# ATSAM3X8E_Main_Controller_-_TR_R1_1.net
KiCad netlist of a schematic drawn in Altium Designer
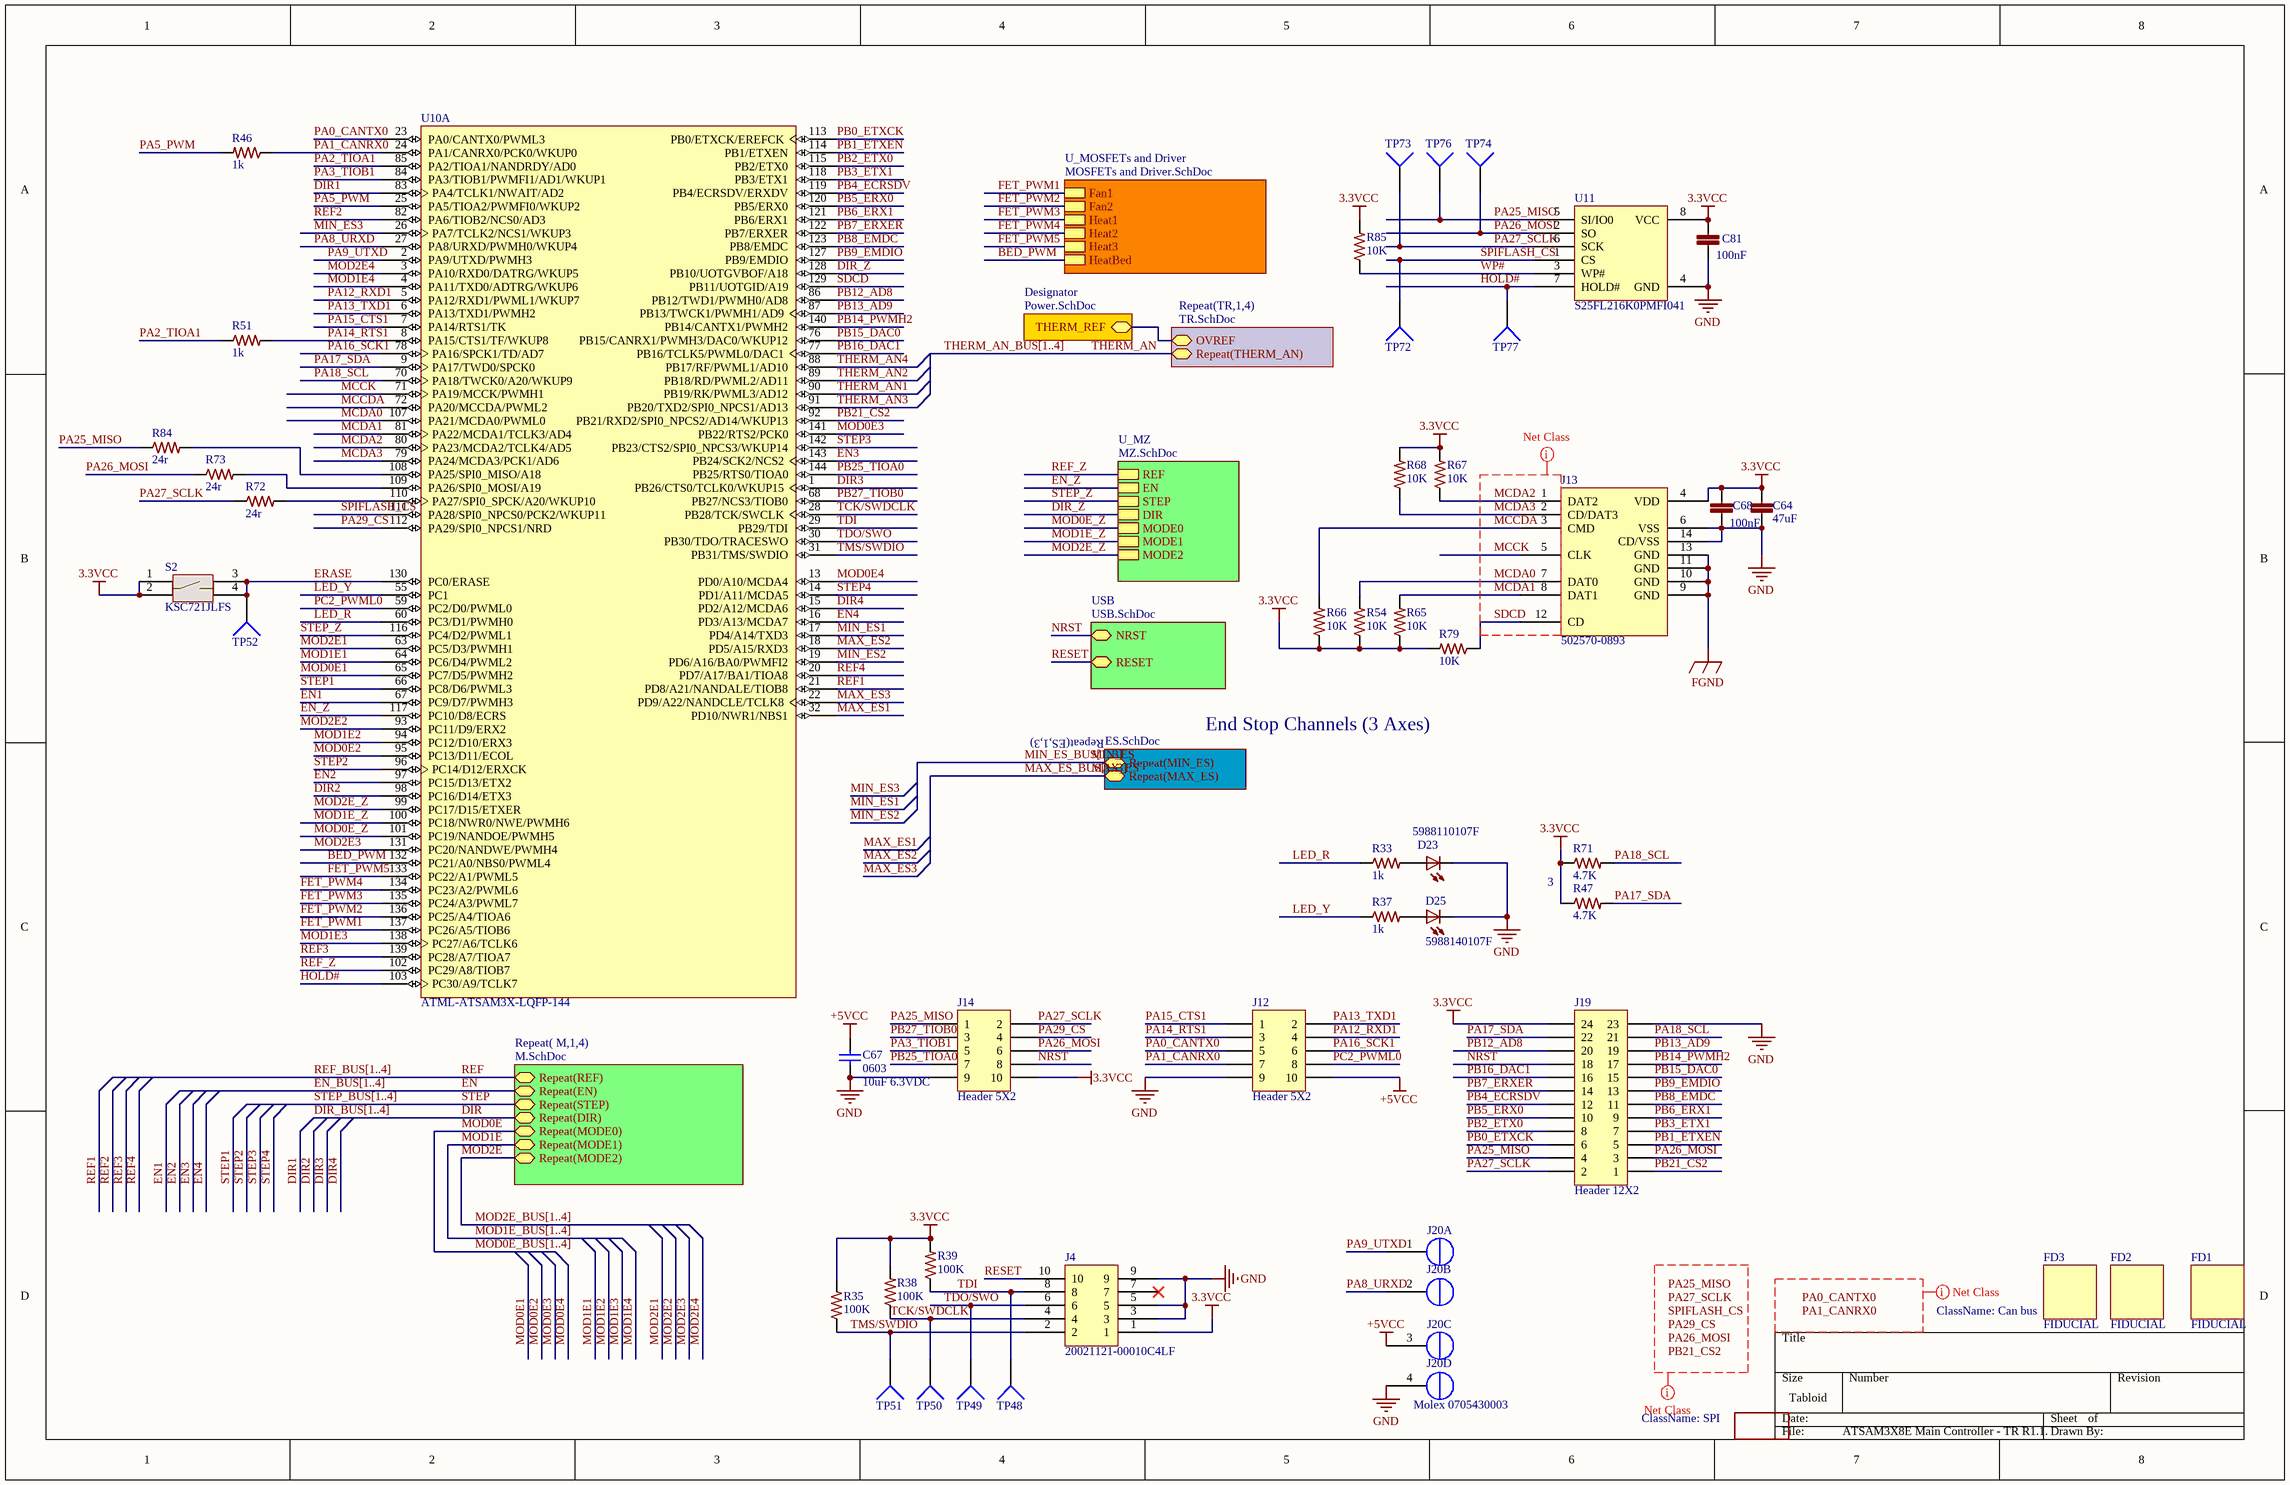
[diagram p0: ATSAM3X8E Main Controller - TR R1.1.SchDoc]

(export (version "E")
  (design (tool "Eeschema 10.0.6"))
  (components
    (comp (ref "C64")
      (value "47uF")
      (footprint "C0805")
      (description "CAP CER 47UF 6.3V 20% X5R 0805")
      (fields
        (field (name "MANUFACTURER") "Samsung")
        (field (name "MANUFACTURERPARTNUMBER") "CL21A476MQCLRNC")
        (field (name "PUBLISHER") "UltiMachine")
      )
      (libsource (lib "Tigershark3D") (part "CL21A476MQCLRNC"))
    )
    (comp (ref "C67")
      (value "0603")
      (footprint "C0603")
      (description "CAP CER 10UF 6.3V 10% JB 0603")
      (fields
        (field (name "MFR PART #") "C1608JB0J106K080AB")
        (field (name "MFR") "TDK")
        (field (name "ALTIUM_VALUE") "10uF 6.3VDC")
      )
      (libsource (lib "Tigershark3D") (part "C1608JB0J106K080AB"))
    )
    (comp (ref "C68")
      (value "100nF")
      (footprint "C0402")
      (description "CAP CER 0402 100nF 16V 10% X7R")
      (fields
        (field (name "MANUFACTURERPARTNUMBER") "GRM155R71C104KA88D")
        (field (name "PUBLISHER") "UltiMachine")
      )
      (libsource (lib "3Delight") (part "GRM155R71C104KA88D"))
    )
    (comp (ref "C81")
      (value "100nF")
      (footprint "C0402")
      (description "CAP CER 0402 100nF 16V 10% X7R")
      (fields
        (field (name "MANUFACTURERPARTNUMBER") "GRM155R71C104KA88D")
        (field (name "PUBLISHER") "UltiMachine")
      )
      (libsource (lib "3Delight") (part "GRM155R71C104KA88D"))
    )
    (comp (ref "D23")
      (value "5988110107F")
      (footprint "LED2012120")
      (description "LED 0805 Red")
      (fields (field (name "PUBLISHER") "UltiMachine"))
      (libsource (lib "3Delight") (part "5988110107F"))
    )
    (comp (ref "D25")
      (value "5988140107F")
      (footprint "LED2012120")
      (description "LED 0805 Yellow")
      (fields (field (name "PUBLISHER") "UltiMachine"))
      (libsource (lib "3Delight") (part "5988140107F"))
    )
    (comp (ref "FD1")
      (value "FIDUCIAL")
      (footprint "FIDUCIAL-1X2")
      (libsource (lib "3Delight") (part "FIDUCIAL"))
    )
    (comp (ref "FD2")
      (value "FIDUCIAL")
      (footprint "FIDUCIAL-1X2")
      (libsource (lib "3Delight") (part "FIDUCIAL"))
    )
    (comp (ref "FD3")
      (value "FIDUCIAL")
      (footprint "FIDUCIAL-1X2")
      (libsource (lib "3Delight") (part "FIDUCIAL"))
    )
    (comp (ref "J4")
      (value "20021121-00010C4LF")
      (footprint "FTSH-105-XX-X-DV")
      (libsource (lib "Adams Altium Library") (part "ARM Cortex JTAG-DEBUG Header"))
    )
    (comp (ref "J12")
      (value "Header 5X2")
      (footprint "HDR2X5")
      (description "Header, 5-Pin, Dual row")
      (fields (field (name "PUBLISHER") "Altium Limited"))
      (libsource (lib "Miscellaneous Connectors") (part "Header 5X2"))
    )
    (comp (ref "J13")
      (value "502570-0893")
      (footprint "502570-0893 - Molex SD")
      (description "microSD 502570-0893 Molex Part")
      (libsource (lib "Tigershark3D") (part "502570-0893"))
    )
    (comp (ref "J14")
      (value "Header 5X2")
      (footprint "HDR2X5")
      (description "Header, 5-Pin, Dual row")
      (fields (field (name "PUBLISHER") "Altium Limited"))
      (libsource (lib "Miscellaneous Connectors") (part "Header 5X2"))
    )
    (comp (ref "J19")
      (value "Header 12X2")
      (footprint "HDR2X12")
      (description "Header, 12-Pin, Dual row")
      (fields (field (name "PUBLISHER") "Altium Limited"))
      (libsource (lib "Miscellaneous Connectors") (part "Header 12X2"))
    )
    (comp (ref "J20")
      (value "Molex 0705430003")
      (footprint "Molex 0705430003")
      (description "Molex 4 Pin Clip Connector")
      (libsource (lib "ZMBo Schematic Library") (part "Molex 0705430003 Alt"))
    )
    (comp (ref "LOGO1")
      (value "OSHW_LOGO_8MILX0150-NT")
      (footprint "OSHW_8X150_NOTEXT")
      (fields (field (name "PUBLISHER") "UltiMachine"))
      (libsource (lib "3Delight") (part "OSHW_LOGO_8MILX0150-NT"))
    )
    (comp (ref "R33")
      (value "1k")
      (footprint "R0402")
      (description "RES 0402 1k 63mW 1%")
      (fields (field (name "PUBLISHER") "UltiMachine"))
      (libsource (lib "3Delight") (part "RK73H1ETTP1001F"))
    )
    (comp (ref "R35")
      (value "100K")
      (footprint "3Delight:R0402")
      (description "RES SMD 100K OHM 1% 1/16W 0402")
      (fields
        (field (name "MANUFACTURER") "Samsung")
        (field (name "MANUFACTURERPARTNUMBER") "RC1005F104CS")
        (field (name "PUBLISHER") "UltiMachine")
      )
      (libsource (lib "Tigershark3D") (part "RC1005F104CS"))
    )
    (comp (ref "R37")
      (value "1k")
      (footprint "R0402")
      (description "RES 0402 1k 63mW 1%")
      (fields (field (name "PUBLISHER") "UltiMachine"))
      (libsource (lib "3Delight") (part "RK73H1ETTP1001F"))
    )
    (comp (ref "R38")
      (value "100K")
      (footprint "3Delight:R0402")
      (description "RES SMD 100K OHM 1% 1/16W 0402")
      (fields
        (field (name "MANUFACTURER") "Samsung")
        (field (name "MANUFACTURERPARTNUMBER") "RC1005F104CS")
        (field (name "PUBLISHER") "UltiMachine")
      )
      (libsource (lib "Tigershark3D") (part "RC1005F104CS"))
    )
    (comp (ref "R39")
      (value "100K")
      (footprint "3Delight:R0402")
      (description "RES SMD 100K OHM 1% 1/16W 0402")
      (fields
        (field (name "MANUFACTURER") "Samsung")
        (field (name "MANUFACTURERPARTNUMBER") "RC1005F104CS")
        (field (name "PUBLISHER") "UltiMachine")
      )
      (libsource (lib "Tigershark3D") (part "RC1005F104CS"))
    )
    (comp (ref "R46")
      (value "1k")
      (footprint "R0402")
      (description "RES 0402 1k 63mW 1%")
      (fields (field (name "PUBLISHER") "UltiMachine"))
      (libsource (lib "3Delight") (part "RK73H1ETTP1001F"))
    )
    (comp (ref "R47")
      (value "4.7K")
      (footprint "R0603")
      (description "RES 0603 4.7K 100mW 1%")
      (fields (field (name "MANUFACTURERPARTNUMBER") "ERJ3EKF4701V") (field (name "PUBLISHER") "UltiMachine"))
      (libsource (lib "3Delight") (part "ERJ3EKF4701V"))
    )
    (comp (ref "R51")
      (value "1k")
      (footprint "R0402")
      (description "RES 0402 1k 63mW 1%")
      (fields (field (name "PUBLISHER") "UltiMachine"))
      (libsource (lib "3Delight") (part "RK73H1ETTP1001F"))
    )
    (comp (ref "R54")
      (value "10K")
      (footprint "R0402")
      (description "RES SMD 10K OHM 1% 1/16W 0402")
      (fields
        (field (name "MANUFACTURERPARTNUMBER") "RC0402FR-0710KP")
        (field (name "PUBLISHER") "UltiMachine")
      )
      (libsource (lib "3Delight") (part "RC0402FR-0710KP"))
    )
    (comp (ref "R65")
      (value "10K")
      (footprint "R0402")
      (description "RES SMD 10K OHM 1% 1/16W 0402")
      (fields
        (field (name "MANUFACTURERPARTNUMBER") "RC0402FR-0710KP")
        (field (name "PUBLISHER") "UltiMachine")
      )
      (libsource (lib "3Delight") (part "RC0402FR-0710KP"))
    )
    (comp (ref "R66")
      (value "10K")
      (footprint "R0402")
      (description "RES SMD 10K OHM 1% 1/16W 0402")
      (fields
        (field (name "MANUFACTURERPARTNUMBER") "RC0402FR-0710KP")
        (field (name "PUBLISHER") "UltiMachine")
      )
      (libsource (lib "3Delight") (part "RC0402FR-0710KP"))
    )
    (comp (ref "R67")
      (value "10K")
      (footprint "R0402")
      (description "RES SMD 10K OHM 1% 1/16W 0402")
      (fields
        (field (name "MANUFACTURERPARTNUMBER") "RC0402FR-0710KP")
        (field (name "PUBLISHER") "UltiMachine")
      )
      (libsource (lib "3Delight") (part "RC0402FR-0710KP"))
    )
    (comp (ref "R68")
      (value "10K")
      (footprint "R0402")
      (description "RES SMD 10K OHM 1% 1/16W 0402")
      (fields
        (field (name "MANUFACTURERPARTNUMBER") "RC0402FR-0710KP")
        (field (name "PUBLISHER") "UltiMachine")
      )
      (libsource (lib "3Delight") (part "RC0402FR-0710KP"))
    )
    (comp (ref "R71")
      (value "4.7K")
      (footprint "R0603")
      (description "RES 0603 4.7K 100mW 1%")
      (fields (field (name "MANUFACTURERPARTNUMBER") "ERJ3EKF4701V") (field (name "PUBLISHER") "UltiMachine"))
      (libsource (lib "3Delight") (part "ERJ3EKF4701V"))
    )
    (comp (ref "R72")
      (value "24r")
      (footprint "R0402")
      (description "Res Thick Film 0402 24 Ohm 1% 0.063W")
      (fields
        (field (name "MANUFACTURERPARTNUMBER") "CRCW0402200KFKED")
        (field (name "PUBLISHER") "UltiMachine")
      )
      (libsource (lib "3Delight") (part "CRCW040224R0FKED"))
    )
    (comp (ref "R73")
      (value "24r")
      (footprint "R0402")
      (description "Res Thick Film 0402 24 Ohm 1% 0.063W")
      (fields
        (field (name "MANUFACTURERPARTNUMBER") "CRCW0402200KFKED")
        (field (name "PUBLISHER") "UltiMachine")
      )
      (libsource (lib "3Delight") (part "CRCW040224R0FKED"))
    )
    (comp (ref "R79")
      (value "10K")
      (footprint "R0402")
      (description "RES SMD 10K OHM 1% 1/16W 0402")
      (fields
        (field (name "MANUFACTURERPARTNUMBER") "RC0402FR-0710KP")
        (field (name "PUBLISHER") "UltiMachine")
      )
      (libsource (lib "3Delight") (part "RC0402FR-0710KP"))
    )
    (comp (ref "R84")
      (value "24r")
      (footprint "R0402")
      (description "Res Thick Film 0402 24 Ohm 1% 0.063W")
      (fields
        (field (name "MANUFACTURERPARTNUMBER") "CRCW0402200KFKED")
        (field (name "PUBLISHER") "UltiMachine")
      )
      (libsource (lib "3Delight") (part "CRCW040224R0FKED"))
    )
    (comp (ref "R85")
      (value "10K")
      (footprint "R0402")
      (description "RES SMD 10K OHM 1% 1/16W 0402")
      (fields
        (field (name "MANUFACTURERPARTNUMBER") "RC0402FR-0710KP")
        (field (name "PUBLISHER") "UltiMachine")
      )
      (libsource (lib "3Delight") (part "RC0402FR-0710KP"))
    )
    (comp (ref "S2")
      (value "KSC721JLFS")
      (footprint "KSC721JLFS")
      (description "Switch SPST 1.7 N / 1.8 N J Bend Surface Mount Tactile Switch")
      (libsource (lib "3Delight") (part "KSC721JLFS"))
    )
    (comp (ref "TP48")
      (value "TP4")
      (footprint "TP-2")
      (description "Socket")
      (fields (field (name "PUBLISHER") "Altium Limited"))
      (libsource (lib "ZMBo Schematic Library") (part "Socket"))
    )
    (comp (ref "TP49")
      (value "TP4")
      (footprint "TP-2")
      (description "Socket")
      (fields (field (name "PUBLISHER") "Altium Limited"))
      (libsource (lib "ZMBo Schematic Library") (part "Socket"))
    )
    (comp (ref "TP50")
      (value "TP4")
      (footprint "TP-2")
      (description "Socket")
      (fields (field (name "PUBLISHER") "Altium Limited"))
      (libsource (lib "ZMBo Schematic Library") (part "Socket"))
    )
    (comp (ref "TP51")
      (value "TP4")
      (footprint "TP-2")
      (description "Socket")
      (fields (field (name "PUBLISHER") "Altium Limited"))
      (libsource (lib "ZMBo Schematic Library") (part "Socket"))
    )
    (comp (ref "TP52")
      (value "TP4")
      (footprint "TP-2")
      (description "Socket")
      (fields (field (name "PUBLISHER") "Altium Limited"))
      (libsource (lib "ZMBo Schematic Library") (part "Socket"))
    )
    (comp (ref "TP72")
      (value "TP4")
      (footprint "TP-2")
      (description "Socket")
      (fields (field (name "PUBLISHER") "Altium Limited"))
      (libsource (lib "ZMBo Schematic Library") (part "Socket"))
    )
    (comp (ref "TP73")
      (value "TP4")
      (footprint "TP-2")
      (description "Socket")
      (fields (field (name "PUBLISHER") "Altium Limited"))
      (libsource (lib "ZMBo Schematic Library") (part "Socket"))
    )
    (comp (ref "TP74")
      (value "TP4")
      (footprint "TP-2")
      (description "Socket")
      (fields (field (name "PUBLISHER") "Altium Limited"))
      (libsource (lib "ZMBo Schematic Library") (part "Socket"))
    )
    (comp (ref "TP76")
      (value "TP4")
      (footprint "TP-2")
      (description "Socket")
      (fields (field (name "PUBLISHER") "Altium Limited"))
      (libsource (lib "ZMBo Schematic Library") (part "Socket"))
    )
    (comp (ref "TP77")
      (value "TP4")
      (footprint "TP-2")
      (description "Socket")
      (fields (field (name "PUBLISHER") "Altium Limited"))
      (libsource (lib "ZMBo Schematic Library") (part "Socket"))
    )
    (comp (ref "U10")
      (value "ATML-ATSAM3X-LQFP-144")
      (footprint "LQFP144_N")
      (libsource (lib "ZMBo Schematic Library") (part "ATML-ATSAM3X-LQFP-144"))
    )
    (comp (ref "U11")
      (value "S25FL216K0PMFI041")
      (footprint "S25FL216K0PMFI041")
      (fields (field (name "DIGIKEY PART NUMBER") "1274-1052-ND"))
      (libsource (lib "Tigershark3D") (part "S25FL216K0PMFI041"))
    )
  )
  (nets
    (net (code "39") (name "+5VCC") (class "Default")
      (node (ref "C67") (pin "2") (pinfunction "2_2") (pintype "passive"))
      (node (ref "J12") (pin "10") (pinfunction "10_10") (pintype "passive"))
      (node (ref "J20") (pin "3") (pinfunction "OUT1A_3") (pintype "passive"))
    )
    (net (code "40") (name "/BED_PWM") (class "Default")
      (node (ref "U10") (pin "132") (pinfunction "PC21/A0/NBS0/PWML4_132") (pintype "bidirectional"))
    )
    (net (code "42") (name "/DIR1") (class "Default")
      (node (ref "U10") (pin "83") (pinfunction "PA4/TCLK1/NWAIT/AD2_83") (pintype "bidirectional"))
    )
    (net (code "43") (name "/DIR2") (class "Default")
      (node (ref "U10") (pin "98") (pinfunction "PC16/D14/ETX3_98") (pintype "bidirectional"))
    )
    (net (code "44") (name "/DIR3") (class "Default")
      (node (ref "U10") (pin "1") (pinfunction "PB26/CTS0/TCLK0/WKUP15_1") (pintype "bidirectional"))
    )
    (net (code "45") (name "/DIR4") (class "Default")
      (node (ref "U10") (pin "15") (pinfunction "PD2/A12/MCDA6_15") (pintype "bidirectional"))
    )
    (net (code "47") (name "/DIR_Z") (class "Default")
      (node (ref "U10") (pin "128") (pinfunction "PB10/UOTGVBOF/A18_128") (pintype "bidirectional"))
    )
    (net (code "49") (name "/EN1") (class "Default")
      (node (ref "U10") (pin "67") (pinfunction "PC9/D7/PWMH3_67") (pintype "bidirectional"))
    )
    (net (code "50") (name "/EN2") (class "Default")
      (node (ref "U10") (pin "97") (pinfunction "PC15/D13/ETX2_97") (pintype "bidirectional"))
    )
    (net (code "51") (name "/EN3") (class "Default")
      (node (ref "U10") (pin "143") (pinfunction "PB24/SCK2/NCS2_143") (pintype "bidirectional"))
    )
    (net (code "52") (name "/EN4") (class "Default")
      (node (ref "U10") (pin "16") (pinfunction "PD3/A13/MCDA7_16") (pintype "bidirectional"))
    )
    (net (code "54") (name "/EN_Z") (class "Default")
      (node (ref "U10") (pin "117") (pinfunction "PC10/D8/ECRS_117") (pintype "bidirectional"))
    )
    (net (code "55") (name "/ERASE") (class "Default")
      (node (ref "S2") (pin "3") (pintype "power_in"))
      (node (ref "S2") (pin "4") (pintype "power_in"))
      (node (ref "TP52") (pin "1") (pinfunction "1_1") (pintype "passive"))
      (node (ref "U10") (pin "130") (pinfunction "PC0/ERASE_130") (pintype "bidirectional"))
    )
    (net (code "56") (name "/FET_PWM1") (class "Default")
      (node (ref "U10") (pin "137") (pinfunction "PC26/A5/TIOB6_137") (pintype "bidirectional"))
    )
    (net (code "57") (name "/FET_PWM2") (class "Default")
      (node (ref "U10") (pin "136") (pinfunction "PC25/A4/TIOA6_136") (pintype "bidirectional"))
    )
    (net (code "58") (name "/FET_PWM3") (class "Default")
      (node (ref "U10") (pin "135") (pinfunction "PC24/A3/PWML7_135") (pintype "bidirectional"))
    )
    (net (code "59") (name "/FET_PWM4") (class "Default")
      (node (ref "U10") (pin "134") (pinfunction "PC23/A2/PWML6_134") (pintype "bidirectional"))
    )
    (net (code "60") (name "/FET_PWM5") (class "Default")
      (node (ref "U10") (pin "133") (pinfunction "PC22/A1/PWML5_133") (pintype "bidirectional"))
    )
    (net (code "61") (name "/HOLD#") (class "Default")
      (node (ref "TP77") (pin "1") (pinfunction "1_1") (pintype "passive"))
      (node (ref "U10") (pin "103") (pinfunction "PC30/A9/TCLK7_103") (pintype "bidirectional"))
      (node (ref "U11") (pin "7") (pinfunction "HOLD#_7") (pintype "passive"))
    )
    (net (code "62") (name "/LED_R") (class "Default")
      (node (ref "R33") (pin "1") (pinfunction "1_1") (pintype "passive"))
      (node (ref "U10") (pin "60") (pinfunction "PC3/D1/PWMH0_60") (pintype "bidirectional"))
    )
    (net (code "63") (name "/LED_Y") (class "Default")
      (node (ref "R37") (pin "1") (pinfunction "1_1") (pintype "passive"))
      (node (ref "U10") (pin "55") (pinfunction "PC1_55") (pintype "bidirectional"))
    )
    (net (code "65") (name "/MAX_ES1") (class "Default")
      (node (ref "U10") (pin "32") (pinfunction "PD10/NWR1/NBS1_32") (pintype "bidirectional"))
    )
    (net (code "66") (name "/MAX_ES2") (class "Default")
      (node (ref "U10") (pin "18") (pinfunction "PD5/A15/RXD3_18") (pintype "bidirectional"))
    )
    (net (code "67") (name "/MAX_ES3") (class "Default")
      (node (ref "U10") (pin "22") (pinfunction "PD9/A22/NANDCLE/TCLK8_22") (pintype "bidirectional"))
    )
    (net (code "69") (name "/MCCDA") (class "Default")
      (node (ref "J13") (pin "3") (pinfunction "CMD_3") (pintype "passive"))
      (node (ref "R66") (pin "2") (pinfunction "2_2") (pintype "passive"))
      (node (ref "U10") (pin "72") (pinfunction "PA20/MCCDA/PWML2_72") (pintype "bidirectional"))
    )
    (net (code "70") (name "/MCCK") (class "Default")
      (node (ref "J13") (pin "5") (pinfunction "CLK_5") (pintype "passive"))
      (node (ref "U10") (pin "71") (pinfunction "PA19/MCCK/PWMH1_71") (pintype "bidirectional"))
    )
    (net (code "71") (name "/MCDA0") (class "Default")
      (node (ref "J13") (pin "7") (pinfunction "DAT0_7") (pintype "passive"))
      (node (ref "R54") (pin "2") (pinfunction "2_2") (pintype "passive"))
      (node (ref "U10") (pin "107") (pinfunction "PA21/MCDA0/PWML0_107") (pintype "bidirectional"))
    )
    (net (code "72") (name "/MCDA1") (class "Default")
      (node (ref "J13") (pin "8") (pinfunction "DAT1_8") (pintype "passive"))
      (node (ref "R65") (pin "2") (pinfunction "2_2") (pintype "passive"))
      (node (ref "U10") (pin "81") (pinfunction "PA22/MCDA1/TCLK3/AD4_81") (pintype "bidirectional"))
    )
    (net (code "73") (name "/MCDA2") (class "Default")
      (node (ref "J13") (pin "1") (pinfunction "DAT2_1") (pintype "passive"))
      (node (ref "R67") (pin "1") (pinfunction "1_1") (pintype "passive"))
      (node (ref "U10") (pin "80") (pinfunction "PA23/MCDA2/TCLK4/AD5_80") (pintype "bidirectional"))
    )
    (net (code "74") (name "/MCDA3") (class "Default")
      (node (ref "J13") (pin "2") (pinfunction "CD/DAT3_2") (pintype "passive"))
      (node (ref "R68") (pin "1") (pinfunction "1_1") (pintype "passive"))
      (node (ref "U10") (pin "79") (pinfunction "PA24/MCDA3/PCK1/AD6_79") (pintype "bidirectional"))
    )
    (net (code "76") (name "/MIN_ES1") (class "Default")
      (node (ref "U10") (pin "17") (pinfunction "PD4/A14/TXD3_17") (pintype "bidirectional"))
    )
    (net (code "77") (name "/MIN_ES2") (class "Default")
      (node (ref "U10") (pin "19") (pinfunction "PD6/A16/BA0/PWMFI2_19") (pintype "bidirectional"))
    )
    (net (code "78") (name "/MIN_ES3") (class "Default")
      (node (ref "U10") (pin "26") (pinfunction "PA7/TCLK2/NCS1/WKUP3_26") (pintype "bidirectional"))
    )
    (net (code "81") (name "/MOD0E1") (class "Default")
      (node (ref "U10") (pin "65") (pinfunction "PC7/D5/PWMH2_65") (pintype "bidirectional"))
    )
    (net (code "82") (name "/MOD0E2") (class "Default")
      (node (ref "U10") (pin "95") (pinfunction "PC13/D11/ECOL_95") (pintype "bidirectional"))
    )
    (net (code "83") (name "/MOD0E3") (class "Default")
      (node (ref "U10") (pin "141") (pinfunction "PB22/RTS2/PCK0_141") (pintype "bidirectional"))
    )
    (net (code "84") (name "/MOD0E4") (class "Default")
      (node (ref "U10") (pin "13") (pinfunction "PD0/A10/MCDA4_13") (pintype "bidirectional"))
    )
    (net (code "86") (name "/MOD0E_Z") (class "Default")
      (node (ref "U10") (pin "101") (pinfunction "PC19/NANDOE/PWMH5_101") (pintype "bidirectional"))
    )
    (net (code "88") (name "/MOD1E1") (class "Default")
      (node (ref "U10") (pin "64") (pinfunction "PC6/D4/PWML2_64") (pintype "bidirectional"))
    )
    (net (code "89") (name "/MOD1E2") (class "Default")
      (node (ref "U10") (pin "94") (pinfunction "PC12/D10/ERX3_94") (pintype "bidirectional"))
    )
    (net (code "90") (name "/MOD1E3") (class "Default")
      (node (ref "U10") (pin "138") (pinfunction "PC27/A6/TCLK6_138") (pintype "bidirectional"))
    )
    (net (code "91") (name "/MOD1E4") (class "Default")
      (node (ref "U10") (pin "4") (pinfunction "PA11/TXD0/ADTRG/WKUP6_4") (pintype "bidirectional"))
    )
    (net (code "93") (name "/MOD1E_Z") (class "Default")
      (node (ref "U10") (pin "100") (pinfunction "PC18/NWR0/NWE/PWMH6_100") (pintype "bidirectional"))
    )
    (net (code "95") (name "/MOD2E1") (class "Default")
      (node (ref "U10") (pin "63") (pinfunction "PC5/D3/PWMH1_63") (pintype "bidirectional"))
    )
    (net (code "96") (name "/MOD2E2") (class "Default")
      (node (ref "U10") (pin "93") (pinfunction "PC11/D9/ERX2_93") (pintype "bidirectional"))
    )
    (net (code "97") (name "/MOD2E3") (class "Default")
      (node (ref "U10") (pin "131") (pinfunction "PC20/NANDWE/PWMH4_131") (pintype "bidirectional"))
    )
    (net (code "98") (name "/MOD2E4") (class "Default")
      (node (ref "U10") (pin "3") (pinfunction "PA10/RXD0/DATRG/WKUP5_3") (pintype "bidirectional"))
    )
    (net (code "100") (name "/MOD2E_Z") (class "Default")
      (node (ref "U10") (pin "99") (pinfunction "PC17/D15/ETXER_99") (pintype "bidirectional"))
    )
    (net (code "101") (name "/NRST") (class "Default")
      (node (ref "J14") (pin "8") (pinfunction "8_8") (pintype "passive"))
      (node (ref "J19") (pin "18") (pinfunction "18_18") (pintype "passive"))
    )
    (net (code "103") (name "/PA0_CANTX0") (class "Default")
      (node (ref "J12") (pin "5") (pinfunction "5_5") (pintype "passive"))
      (node (ref "U10") (pin "23") (pinfunction "PA0/CANTX0/PWML3_23") (pintype "bidirectional"))
    )
    (net (code "104") (name "/PA1_CANRX0") (class "Default")
      (node (ref "J12") (pin "7") (pinfunction "7_7") (pintype "passive"))
      (node (ref "R46") (pin "1") (pinfunction "1_1") (pintype "passive"))
      (node (ref "U10") (pin "24") (pinfunction "PA1/CANRX0/PCK0/WKUP0_24") (pintype "bidirectional"))
    )
    (net (code "105") (name "/PA2_TIOA1") (class "Default")
      (node (ref "R51") (pin "1") (pinfunction "1_1") (pintype "passive"))
      (node (ref "U10") (pin "85") (pinfunction "PA2/TIOA1/NANDRDY/AD0_85") (pintype "bidirectional"))
    )
    (net (code "106") (name "/PA3_TIOB1") (class "Default")
      (node (ref "J14") (pin "5") (pinfunction "5_5") (pintype "passive"))
      (node (ref "U10") (pin "84") (pinfunction "PA3/TIOB1/PWMFI1/AD1/WKUP1_84") (pintype "bidirectional"))
    )
    (net (code "107") (name "/PA5_PWM") (class "Default")
      (node (ref "R46") (pin "2") (pinfunction "2_2") (pintype "passive"))
      (node (ref "U10") (pin "25") (pinfunction "PA5/TIOA2/PWMFI0/WKUP2_25") (pintype "bidirectional"))
    )
    (net (code "108") (name "/PA8_URXD") (class "Default")
      (node (ref "J20") (pin "2") (pinfunction "OUT2A_2") (pintype "passive"))
      (node (ref "U10") (pin "27") (pinfunction "PA8/URXD/PWMH0/WKUP4_27") (pintype "bidirectional"))
    )
    (net (code "109") (name "/PA9_UTXD") (class "Default")
      (node (ref "J20") (pin "1") (pinfunction "OUT2B_1") (pintype "passive"))
      (node (ref "U10") (pin "2") (pinfunction "PA9/UTXD/PWMH3_2") (pintype "bidirectional"))
    )
    (net (code "110") (name "/PA12_RXD1") (class "Default")
      (node (ref "J12") (pin "4") (pinfunction "4_4") (pintype "passive"))
      (node (ref "U10") (pin "5") (pinfunction "PA12/RXD1/PWML1/WKUP7_5") (pintype "bidirectional"))
    )
    (net (code "111") (name "/PA13_TXD1") (class "Default")
      (node (ref "J12") (pin "2") (pinfunction "2_2") (pintype "passive"))
      (node (ref "U10") (pin "6") (pinfunction "PA13/TXD1/PWMH2_6") (pintype "bidirectional"))
    )
    (net (code "112") (name "/PA14_RTS1") (class "Default")
      (node (ref "J12") (pin "3") (pinfunction "3_3") (pintype "passive"))
      (node (ref "R51") (pin "2") (pinfunction "2_2") (pintype "passive"))
      (node (ref "U10") (pin "8") (pinfunction "PA15/CTS1/TF/WKUP8_8") (pintype "bidirectional"))
    )
    (net (code "113") (name "/PA15_CTS1") (class "Default")
      (node (ref "J12") (pin "1") (pinfunction "1_1") (pintype "passive"))
      (node (ref "U10") (pin "7") (pinfunction "PA14/RTS1/TK_7") (pintype "bidirectional"))
    )
    (net (code "114") (name "/PA16_SCK1") (class "Default")
      (node (ref "J12") (pin "6") (pinfunction "6_6") (pintype "passive"))
      (node (ref "U10") (pin "78") (pinfunction "PA16/SPCK1/TD/AD7_78") (pintype "bidirectional"))
    )
    (net (code "115") (name "/PA17_SDA") (class "Default")
      (node (ref "J19") (pin "22") (pinfunction "22_22") (pintype "passive"))
      (node (ref "R47") (pin "2") (pinfunction "2_2") (pintype "passive"))
      (node (ref "U10") (pin "9") (pinfunction "PA17/TWD0/SPCK0_9") (pintype "bidirectional"))
    )
    (net (code "116") (name "/PA18_SCL") (class "Default")
      (node (ref "J19") (pin "21") (pinfunction "21_21") (pintype "passive"))
      (node (ref "R71") (pin "2") (pinfunction "2_2") (pintype "passive"))
      (node (ref "U10") (pin "70") (pinfunction "PA18/TWCK0/A20/WKUP9_70") (pintype "bidirectional"))
    )
    (net (code "117") (name "/PA25_MISO") (class "Default")
      (node (ref "J14") (pin "1") (pinfunction "1_1") (pintype "passive"))
      (node (ref "J19") (pin "4") (pinfunction "4_4") (pintype "passive"))
      (node (ref "R84") (pin "1") (pinfunction "1_1") (pintype "passive"))
      (node (ref "TP76") (pin "1") (pinfunction "1_1") (pintype "passive"))
      (node (ref "U11") (pin "5") (pinfunction "SI/IO0_5") (pintype "passive"))
    )
    (net (code "118") (name "/PA26_MOSI") (class "Default")
      (node (ref "J14") (pin "6") (pinfunction "6_6") (pintype "passive"))
      (node (ref "J19") (pin "3") (pinfunction "3_3") (pintype "passive"))
      (node (ref "R73") (pin "1") (pinfunction "1_1") (pintype "passive"))
      (node (ref "TP74") (pin "1") (pinfunction "1_1") (pintype "passive"))
      (node (ref "U11") (pin "2") (pinfunction "SO_2") (pintype "passive"))
    )
    (net (code "119") (name "/PA27_SCLK") (class "Default")
      (node (ref "J14") (pin "2") (pinfunction "2_2") (pintype "passive"))
      (node (ref "J19") (pin "2") (pinfunction "2_2") (pintype "passive"))
      (node (ref "R72") (pin "1") (pinfunction "1_1") (pintype "passive"))
      (node (ref "TP73") (pin "1") (pinfunction "1_1") (pintype "passive"))
      (node (ref "U11") (pin "6") (pinfunction "SCK_6") (pintype "passive"))
    )
    (net (code "120") (name "/PA29_CS") (class "Default")
      (node (ref "J14") (pin "4") (pinfunction "4_4") (pintype "passive"))
      (node (ref "U10") (pin "112") (pinfunction "PA29/SPI0_NPCS1/NRD_112") (pintype "bidirectional"))
    )
    (net (code "121") (name "/PB0_ETXCK") (class "Default")
      (node (ref "J19") (pin "6") (pinfunction "6_6") (pintype "passive"))
      (node (ref "U10") (pin "113") (pinfunction "PB0/ETXCK/EREFCK_113") (pintype "bidirectional"))
    )
    (net (code "122") (name "/PB1_ETXEN") (class "Default")
      (node (ref "J19") (pin "5") (pinfunction "5_5") (pintype "passive"))
      (node (ref "U10") (pin "114") (pinfunction "PB1/ETXEN_114") (pintype "bidirectional"))
    )
    (net (code "123") (name "/PB2_ETX0") (class "Default")
      (node (ref "J19") (pin "8") (pinfunction "8_8") (pintype "passive"))
      (node (ref "U10") (pin "115") (pinfunction "PB2/ETX0_115") (pintype "bidirectional"))
    )
    (net (code "124") (name "/PB3_ETX1") (class "Default")
      (node (ref "J19") (pin "7") (pinfunction "7_7") (pintype "passive"))
      (node (ref "U10") (pin "118") (pinfunction "PB3/ETX1_118") (pintype "bidirectional"))
    )
    (net (code "125") (name "/PB4_ECRSDV") (class "Default")
      (node (ref "J19") (pin "12") (pinfunction "12_12") (pintype "passive"))
      (node (ref "U10") (pin "119") (pinfunction "PB4/ECRSDV/ERXDV_119") (pintype "bidirectional"))
    )
    (net (code "126") (name "/PB5_ERX0") (class "Default")
      (node (ref "J19") (pin "10") (pinfunction "10_10") (pintype "passive"))
      (node (ref "U10") (pin "120") (pinfunction "PB5/ERX0_120") (pintype "bidirectional"))
    )
    (net (code "127") (name "/PB6_ERX1") (class "Default")
      (node (ref "J19") (pin "9") (pinfunction "9_9") (pintype "passive"))
      (node (ref "U10") (pin "121") (pinfunction "PB6/ERX1_121") (pintype "bidirectional"))
    )
    (net (code "128") (name "/PB7_ERXER") (class "Default")
      (node (ref "J19") (pin "14") (pinfunction "14_14") (pintype "passive"))
      (node (ref "U10") (pin "122") (pinfunction "PB7/ERXER_122") (pintype "bidirectional"))
    )
    (net (code "129") (name "/PB8_EMDC") (class "Default")
      (node (ref "J19") (pin "11") (pinfunction "11_11") (pintype "passive"))
      (node (ref "U10") (pin "123") (pinfunction "PB8/EMDC_123") (pintype "bidirectional"))
    )
    (net (code "130") (name "/PB9_EMDIO") (class "Default")
      (node (ref "J19") (pin "13") (pinfunction "13_13") (pintype "passive"))
      (node (ref "U10") (pin "127") (pinfunction "PB9/EMDIO_127") (pintype "bidirectional"))
    )
    (net (code "131") (name "/PB12_AD8") (class "Default")
      (node (ref "J19") (pin "20") (pinfunction "20_20") (pintype "passive"))
      (node (ref "U10") (pin "86") (pinfunction "PB12/TWD1/PWMH0/AD8_86") (pintype "bidirectional"))
    )
    (net (code "132") (name "/PB13_AD9") (class "Default")
      (node (ref "J19") (pin "19") (pinfunction "19_19") (pintype "passive"))
      (node (ref "U10") (pin "87") (pinfunction "PB13/TWCK1/PWMH1/AD9_87") (pintype "bidirectional"))
    )
    (net (code "133") (name "/PB14_PWMH2") (class "Default")
      (node (ref "J19") (pin "17") (pinfunction "17_17") (pintype "passive"))
      (node (ref "U10") (pin "140") (pinfunction "PB14/CANTX1/PWMH2_140") (pintype "bidirectional"))
    )
    (net (code "134") (name "/PB15_DAC0") (class "Default")
      (node (ref "J19") (pin "15") (pinfunction "15_15") (pintype "passive"))
      (node (ref "U10") (pin "76") (pinfunction "PB15/CANRX1/PWMH3/DAC0/WKUP12_76") (pintype "bidirectional"))
    )
    (net (code "135") (name "/PB16_DAC1") (class "Default")
      (node (ref "J19") (pin "16") (pinfunction "16_16") (pintype "passive"))
      (node (ref "U10") (pin "77") (pinfunction "PB16/TCLK5/PWML0/DAC1_77") (pintype "bidirectional"))
    )
    (net (code "136") (name "/PB21_CS2") (class "Default")
      (node (ref "J19") (pin "1") (pinfunction "1_1") (pintype "passive"))
      (node (ref "U10") (pin "92") (pinfunction "PB21/RXD2/SPI0_NPCS2/AD14/WKUP13_92") (pintype "bidirectional"))
    )
    (net (code "137") (name "/PB25_TIOA0") (class "Default")
      (node (ref "J14") (pin "7") (pinfunction "7_7") (pintype "passive"))
      (node (ref "U10") (pin "144") (pinfunction "PB25/RTS0/TIOA0_144") (pintype "bidirectional"))
    )
    (net (code "138") (name "/PB27_TIOB0") (class "Default")
      (node (ref "J14") (pin "3") (pinfunction "3_3") (pintype "passive"))
      (node (ref "U10") (pin "68") (pinfunction "PB27/NCS3/TIOB0_68") (pintype "bidirectional"))
    )
    (net (code "139") (name "/PC2_PWML0") (class "Default")
      (node (ref "J12") (pin "8") (pinfunction "8_8") (pintype "passive"))
      (node (ref "U10") (pin "59") (pinfunction "PC2/D0/PWML0_59") (pintype "bidirectional"))
    )
    (net (code "141") (name "/REF1") (class "Default")
      (node (ref "U10") (pin "21") (pinfunction "PD8/A21/NANDALE/TIOB8_21") (pintype "bidirectional"))
    )
    (net (code "142") (name "/REF2") (class "Default")
      (node (ref "U10") (pin "82") (pinfunction "PA6/TIOB2/NCS0/AD3_82") (pintype "bidirectional"))
    )
    (net (code "143") (name "/REF3") (class "Default")
      (node (ref "U10") (pin "139") (pinfunction "PC28/A7/TIOA7_139") (pintype "bidirectional"))
    )
    (net (code "144") (name "/REF4") (class "Default")
      (node (ref "U10") (pin "20") (pinfunction "PD7/A17/BA1/TIOA8_20") (pintype "bidirectional"))
    )
    (net (code "146") (name "/REF_Z") (class "Default")
      (node (ref "U10") (pin "102") (pinfunction "PC29/A8/TIOB7_102") (pintype "bidirectional"))
    )
    (net (code "147") (name "/RESET") (class "Default")
      (node (ref "J4") (pin "10") (pinfunction "10_10") (pintype "passive"))
    )
    (net (code "148") (name "/SDCD") (class "Default")
      (node (ref "J13") (pin "12") (pinfunction "CD_12") (pintype "passive"))
      (node (ref "R79") (pin "1") (pinfunction "1_1") (pintype "passive"))
      (node (ref "U10") (pin "129") (pinfunction "PB11/UOTGID/A19_129") (pintype "bidirectional"))
    )
    (net (code "149") (name "/SPIFLASH_CS") (class "Default")
      (node (ref "TP72") (pin "1") (pinfunction "1_1") (pintype "passive"))
      (node (ref "U10") (pin "111") (pinfunction "PA28/SPI0_NPCS0/PCK2/WKUP11_111") (pintype "bidirectional"))
      (node (ref "U11") (pin "1") (pinfunction "CS_1") (pintype "passive"))
    )
    (net (code "151") (name "/STEP1") (class "Default")
      (node (ref "U10") (pin "66") (pinfunction "PC8/D6/PWML3_66") (pintype "bidirectional"))
    )
    (net (code "152") (name "/STEP2") (class "Default")
      (node (ref "U10") (pin "96") (pinfunction "PC14/D12/ERXCK_96") (pintype "bidirectional"))
    )
    (net (code "153") (name "/STEP3") (class "Default")
      (node (ref "U10") (pin "142") (pinfunction "PB23/CTS2/SPI0_NPCS3/WKUP14_142") (pintype "bidirectional"))
    )
    (net (code "154") (name "/STEP4") (class "Default")
      (node (ref "U10") (pin "14") (pinfunction "PD1/A11/MCDA5_14") (pintype "bidirectional"))
    )
    (net (code "156") (name "/STEP_Z") (class "Default")
      (node (ref "U10") (pin "116") (pinfunction "PC4/D2/PWML1_116") (pintype "bidirectional"))
    )
    (net (code "157") (name "/TCK{slash}SWDCLK") (class "Default")
      (node (ref "J4") (pin "4") (pinfunction "4_4") (pintype "passive"))
      (node (ref "R38") (pin "1") (pinfunction "1_1") (pintype "passive"))
      (node (ref "TP50") (pin "1") (pinfunction "1_1") (pintype "passive"))
      (node (ref "U10") (pin "28") (pinfunction "PB28/TCK/SWCLK_28") (pintype "bidirectional"))
    )
    (net (code "158") (name "/TDI") (class "Default")
      (node (ref "J4") (pin "8") (pinfunction "8_8") (pintype "passive"))
      (node (ref "R39") (pin "1") (pinfunction "1_1") (pintype "passive"))
      (node (ref "TP48") (pin "1") (pinfunction "1_1") (pintype "passive"))
      (node (ref "U10") (pin "29") (pinfunction "PB29/TDI_29") (pintype "bidirectional"))
    )
    (net (code "159") (name "/TDO{slash}SWO") (class "Default")
      (node (ref "J4") (pin "6") (pinfunction "6_6") (pintype "passive"))
      (node (ref "TP49") (pin "1") (pinfunction "1_1") (pintype "passive"))
      (node (ref "U10") (pin "30") (pinfunction "PB30/TDO/TRACESWO_30") (pintype "bidirectional"))
    )
    (net (code "161") (name "/THERM_AN1") (class "Default")
      (node (ref "U10") (pin "90") (pinfunction "PB19/RK/PWML3/AD12_90") (pintype "bidirectional"))
    )
    (net (code "162") (name "/THERM_AN2") (class "Default")
      (node (ref "U10") (pin "89") (pinfunction "PB18/RD/PWML2/AD11_89") (pintype "bidirectional"))
    )
    (net (code "163") (name "/THERM_AN3") (class "Default")
      (node (ref "U10") (pin "91") (pinfunction "PB20/TXD2/SPI0_NPCS1/AD13_91") (pintype "bidirectional"))
    )
    (net (code "164") (name "/THERM_AN4") (class "Default")
      (node (ref "U10") (pin "88") (pinfunction "PB17/RF/PWML1/AD10_88") (pintype "bidirectional"))
    )
    (net (code "166") (name "/TMS{slash}SWDIO") (class "Default")
      (node (ref "J4") (pin "2") (pinfunction "2_2") (pintype "passive"))
      (node (ref "R35") (pin "1") (pinfunction "1_1") (pintype "passive"))
      (node (ref "TP51") (pin "1") (pinfunction "1_1") (pintype "passive"))
      (node (ref "U10") (pin "31") (pinfunction "PB31/TMS/SWDIO_31") (pintype "bidirectional"))
    )
    (net (code "167") (name "/WP#") (class "Default")
      (node (ref "R85") (pin "1") (pinfunction "1_1") (pintype "passive"))
      (node (ref "U11") (pin "3") (pinfunction "WP#_3") (pintype "passive"))
    )
    (net (code "168") (name "3.3VCC") (class "Default")
      (node (ref "C64") (pin "1") (pinfunction "1_1") (pintype "passive"))
      (node (ref "C68") (pin "1") (pinfunction "1_1") (pintype "passive"))
      (node (ref "C81") (pin "1") (pinfunction "1_1") (pintype "passive"))
      (node (ref "J13") (pin "4") (pinfunction "VDD_4") (pintype "passive"))
      (node (ref "J14") (pin "10") (pinfunction "10_10") (pintype "passive"))
      (node (ref "J19") (pin "24") (pinfunction "24_24") (pintype "passive"))
      (node (ref "J4") (pin "1") (pinfunction "1_1") (pintype "passive"))
      (node (ref "R35") (pin "2") (pinfunction "2_2") (pintype "passive"))
      (node (ref "R38") (pin "2") (pinfunction "2_2") (pintype "passive"))
      (node (ref "R39") (pin "2") (pinfunction "2_2") (pintype "passive"))
      (node (ref "R47") (pin "1") (pinfunction "1_1") (pintype "passive"))
      (node (ref "R54") (pin "1") (pinfunction "1_1") (pintype "passive"))
      (node (ref "R65") (pin "1") (pinfunction "1_1") (pintype "passive"))
      (node (ref "R66") (pin "1") (pinfunction "1_1") (pintype "passive"))
      (node (ref "R67") (pin "2") (pinfunction "2_2") (pintype "passive"))
      (node (ref "R68") (pin "2") (pinfunction "2_2") (pintype "passive"))
      (node (ref "R71") (pin "1") (pinfunction "1_1") (pintype "passive"))
      (node (ref "R79") (pin "2") (pinfunction "2_2") (pintype "passive"))
      (node (ref "R85") (pin "2") (pinfunction "2_2") (pintype "passive"))
      (node (ref "S2") (pin "1") (pintype "power_in"))
      (node (ref "S2") (pin "2") (pintype "power_in"))
      (node (ref "U11") (pin "8") (pinfunction "VCC_8") (pintype "passive"))
    )
    (net (code "169") (name "FGND") (class "Default")
      (node (ref "J13") (pin "10") (pinfunction "GND_10") (pintype "passive"))
      (node (ref "J13") (pin "11") (pinfunction "GND_11") (pintype "passive"))
      (node (ref "J13") (pin "13") (pinfunction "GND_13") (pintype "passive"))
      (node (ref "J13") (pin "9") (pinfunction "GND_9") (pintype "passive"))
    )
    (net (code "170") (name "GND") (class "Default")
      (node (ref "C64") (pin "2") (pinfunction "2_2") (pintype "passive"))
      (node (ref "C67") (pin "1") (pinfunction "1_1") (pintype "passive"))
      (node (ref "C68") (pin "2") (pinfunction "2_2") (pintype "passive"))
      (node (ref "C81") (pin "2") (pinfunction "2_2") (pintype "passive"))
      (node (ref "D23") (pin "C") (pinfunction "C_C") (pintype "passive"))
      (node (ref "D25") (pin "C") (pinfunction "C_C") (pintype "passive"))
      (node (ref "J12") (pin "9") (pinfunction "9_9") (pintype "passive"))
      (node (ref "J13") (pin "14") (pinfunction "CD/VSS_14") (pintype "power_in"))
      (node (ref "J13") (pin "6") (pinfunction "VSS_6") (pintype "passive"))
      (node (ref "J14") (pin "9") (pinfunction "9_9") (pintype "passive"))
      (node (ref "J19") (pin "23") (pinfunction "23_23") (pintype "passive"))
      (node (ref "J20") (pin "4") (pinfunction "OUT1B_4") (pintype "passive"))
      (node (ref "J4") (pin "3") (pinfunction "3_3") (pintype "passive"))
      (node (ref "J4") (pin "5") (pinfunction "5_5") (pintype "passive"))
      (node (ref "J4") (pin "9") (pinfunction "9_9") (pintype "passive"))
      (node (ref "U11") (pin "4") (pinfunction "GND_4") (pintype "passive"))
    )
    (net (code "171") (name "Net-(D23-PadA)") (class "Default")
      (node (ref "D23") (pin "A") (pinfunction "A_A") (pintype "passive"))
      (node (ref "R33") (pin "2") (pinfunction "2_2") (pintype "passive"))
    )
    (net (code "172") (name "Net-(D25-PadA)") (class "Default")
      (node (ref "D25") (pin "A") (pinfunction "A_A") (pintype "passive"))
      (node (ref "R37") (pin "2") (pinfunction "2_2") (pintype "passive"))
    )
    (net (code "173") (name "Net-(U10A-PA25{slash}SPI0_MISO{slash}A18)") (class "Default")
      (node (ref "R84") (pin "2") (pinfunction "2_2") (pintype "passive"))
      (node (ref "U10") (pin "108") (pinfunction "PA25/SPI0_MISO/A18_108") (pintype "bidirectional"))
    )
    (net (code "174") (name "Net-(U10A-PA26{slash}SPI0_MOSI{slash}A19)") (class "Default")
      (node (ref "R73") (pin "2") (pinfunction "2_2") (pintype "passive"))
      (node (ref "U10") (pin "109") (pinfunction "PA26/SPI0_MOSI/A19_109") (pintype "bidirectional"))
    )
    (net (code "175") (name "Net-(U10A-PA27{slash}SPI0_SPCK{slash}A20{slash}WKUP10)") (class "Default")
      (node (ref "R72") (pin "2") (pinfunction "2_2") (pintype "passive"))
      (node (ref "U10") (pin "110") (pinfunction "PA27/SPI0_SPCK/A20/WKUP10_110") (pintype "bidirectional"))
    )
    (net (code "176") (name "unconnected-(J4-Pad7)") (class "Default")
      (node (ref "J4") (pin "7") (pinfunction "7_7") (pintype "passive+no_connect"))
    )
  )
)
